# Arduino-Teensy-v421_PLUS_ESP-12E.net
KiCad netlist of a schematic drawn in EAGLE
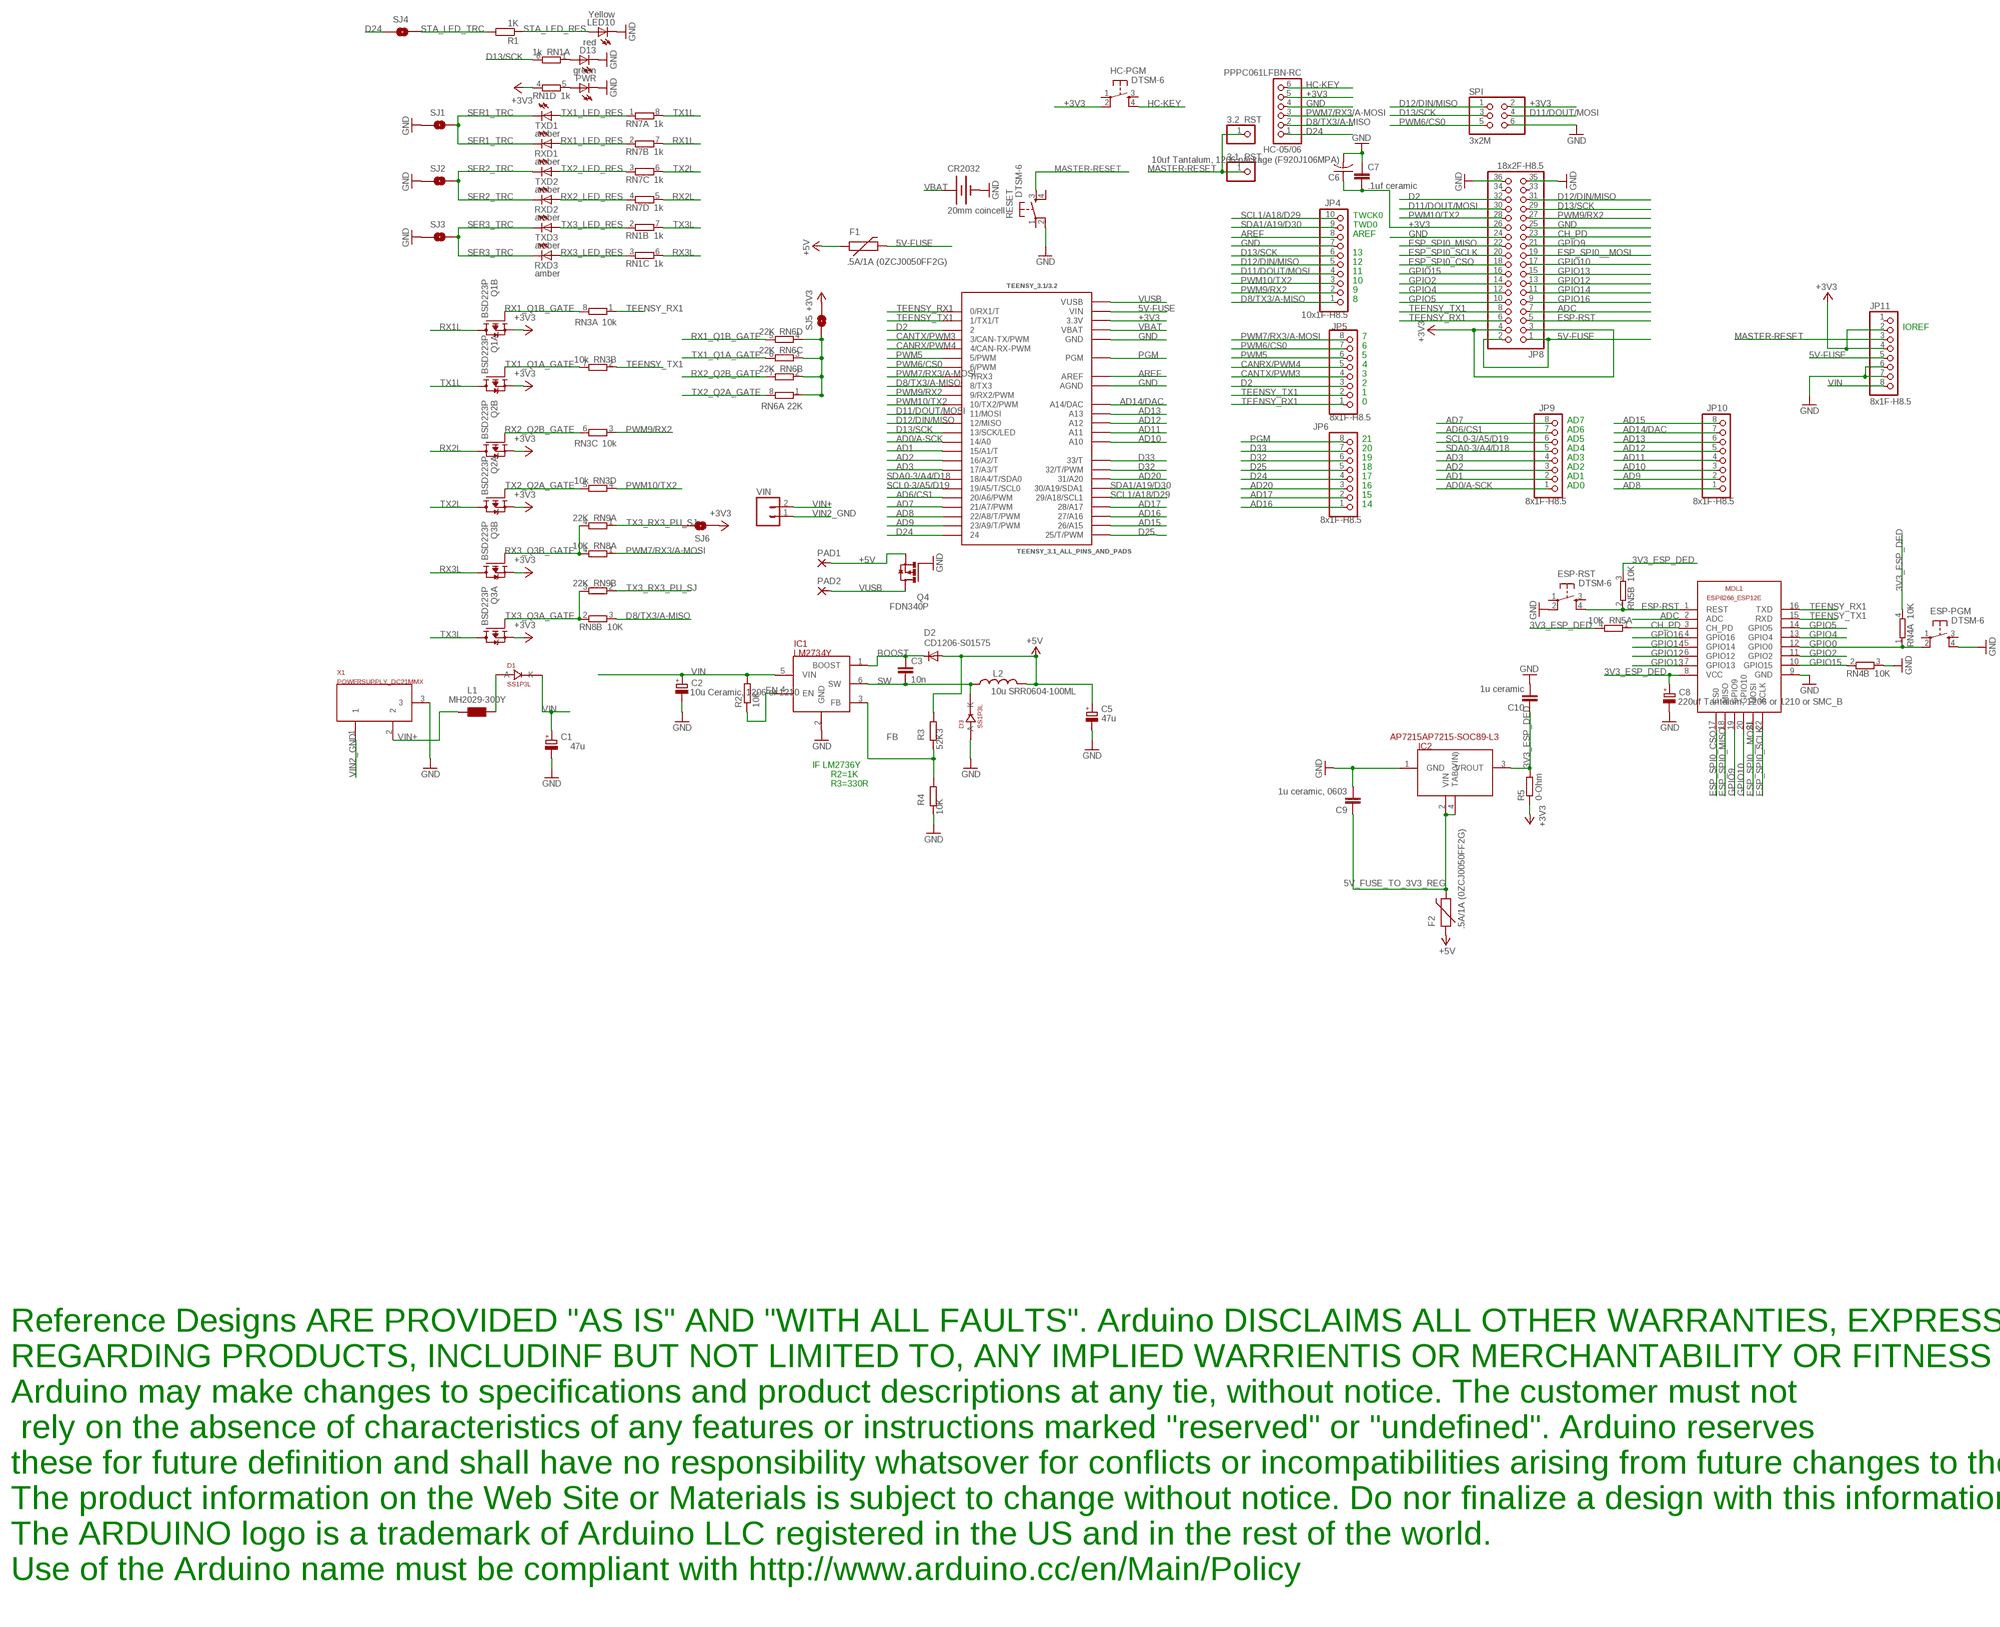
[diagram p0: schematic, sheet 1, part 1 of 2]
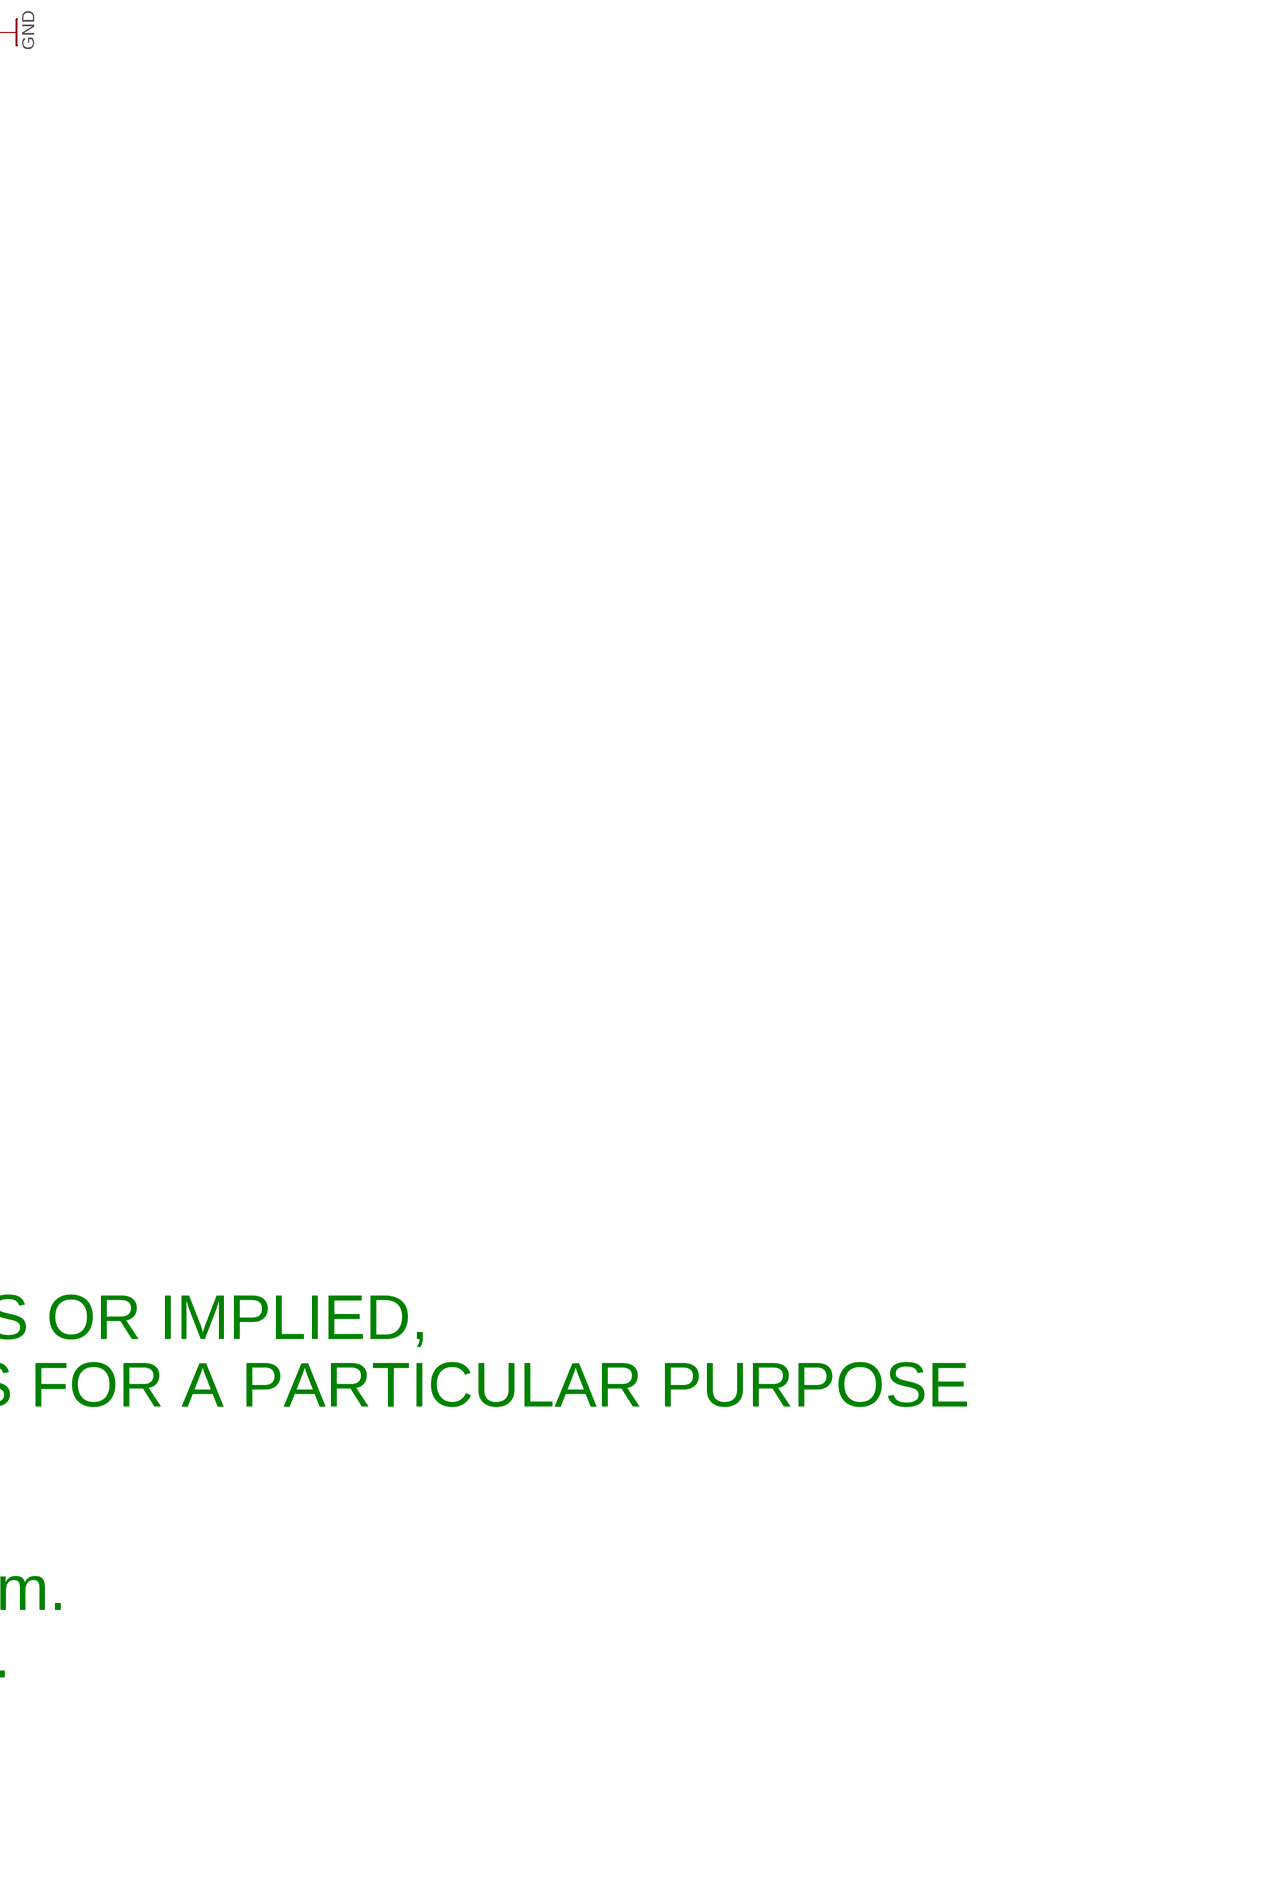
[diagram p1: schematic, sheet 1, part 2 of 2]

(export (version "E")
  (design (tool "Eeschema 10.0.6"))
  (components
    (comp (ref "3.1_RST")
      (value "PINHD-1X1CB")
      (footprint "eagle-import:1X01-CLEANBIG")
      (libsource (lib "eagle-import") (part "PINHD-1X1CB"))
    )
    (comp (ref "3.2_RST")
      (value "PINHD-1X1CB")
      (footprint "eagle-import:1X01-CLEANBIG")
      (libsource (lib "eagle-import") (part "PINHD-1X1CB"))
    )
    (comp (ref "C1")
      (value "47u")
      (footprint "eagle-import:PANASONIC_D")
      (libsource (lib "eagle-import") (part "CPOL-EUD"))
    )
    (comp (ref "C2")
      (value "10u Ceramic, 1206 or 1210")
      (footprint "eagle-import:SMC_B")
      (libsource (lib "eagle-import") (part "CPOL-EUSMCB"))
    )
    (comp (ref "C3")
      (value "10n")
      (footprint "eagle-import:C0603-ROUND")
      (libsource (lib "eagle-import") (part "C-EUC0603"))
    )
    (comp (ref "C5")
      (value "47u")
      (footprint "eagle-import:PANASONIC_D")
      (libsource (lib "eagle-import") (part "CPOL-EUD"))
    )
    (comp (ref "C6")
      (value "10uf Tantalum, 1206 package (F920J106MPA)")
      (footprint "eagle-import:C0805")
      (libsource (lib "eagle-import") (part "C-USC0805"))
    )
    (comp (ref "C7")
      (value ".1uf ceramic")
      (footprint "eagle-import:C0603-ROUND")
      (libsource (lib "eagle-import") (part "C-EUC0603"))
    )
    (comp (ref "C8")
      (value "220uf Tantalum, 1206 or 1210 or SMC_B")
      (footprint "eagle-import:SMC_B")
      (libsource (lib "eagle-import") (part "CPOL-EUSMCB"))
    )
    (comp (ref "C9")
      (value "1u ceramic, 0603")
      (footprint "eagle-import:C0603-ROUND")
      (libsource (lib "eagle-import") (part "C-EUC0603"))
    )
    (comp (ref "C10")
      (value "1u ceramic")
      (footprint "eagle-import:C0603-ROUND")
      (libsource (lib "eagle-import") (part "C-EUC0603"))
    )
    (comp (ref "CR2032")
      (value "20mm coincell")
      (footprint "eagle-import:BATTCON_20MM_4LEGS")
      (libsource (lib "eagle-import") (part "BATTERY20MM_4LEGS"))
    )
    (comp (ref "D1")
      (value "SS1P3L")
      (footprint "eagle-import:DO220AAL")
      (libsource (lib "eagle-import") (part "SS1P3L"))
    )
    (comp (ref "D2")
      (value "CD1206-S01575")
      (footprint "eagle-import:MINIMELF")
      (libsource (lib "eagle-import") (part "DIODE-MINIMELF"))
    )
    (comp (ref "D3")
      (value "SS1P3L")
      (footprint "eagle-import:DO220AAL")
      (libsource (lib "eagle-import") (part "SS1P3L"))
    )
    (comp (ref "D13")
      (value "red")
      (footprint "eagle-import:CHIPLED_0805")
      (libsource (lib "eagle-import") (part "LEDCHIPLED_0805"))
    )
    (comp (ref "ESP-PGM")
      (value "DTSM-6")
      (footprint "eagle-import:DTSM-6")
      (libsource (lib "eagle-import") (part "DTSM-6"))
    )
    (comp (ref "ESP-RST")
      (value "DTSM-6")
      (footprint "eagle-import:DTSM-6")
      (libsource (lib "eagle-import") (part "DTSM-6"))
    )
    (comp (ref "F1")
      (value ".5A/1A (0ZCJ0050FF2G)")
      (footprint "eagle-import:PTC-1206")
      (libsource (lib "eagle-import") (part "PTCSMD"))
    )
    (comp (ref "F2")
      (value ".5A/1A (0ZCJ0050FF2G)")
      (footprint "eagle-import:PTC-1206")
      (libsource (lib "eagle-import") (part "PTCSMD"))
    )
    (comp (ref "HC-05/06")
      (value "PPPC061LFBN-RC")
      (footprint "eagle-import:1X06")
      (libsource (lib "eagle-import") (part "PINHD-1X6"))
    )
    (comp (ref "HC-PGM")
      (value "DTSM-6")
      (footprint "eagle-import:DTSM-6")
      (libsource (lib "eagle-import") (part "DTSM-6"))
    )
    (comp (ref "IC1")
      (value "LM2734Y")
      (footprint "eagle-import:SOT23-6")
      (libsource (lib "eagle-import") (part "LM2736Y"))
    )
    (comp (ref "IC2")
      (value "AP7215AP7215-SOC89-L3")
      (footprint "eagle-import:SOC89-L3")
      (libsource (lib "eagle-import") (part "AP7215AP7215-SOC89-L3"))
    )
    (comp (ref "JP4")
      (value "10x1F-H8.5")
      (footprint "eagle-import:1X10")
      (libsource (lib "eagle-import") (part "PINHD-1X10"))
    )
    (comp (ref "JP5")
      (value "8x1F-H8.5")
      (footprint "eagle-import:1X08")
      (libsource (lib "eagle-import") (part "PINHD-1X8"))
    )
    (comp (ref "JP6")
      (value "8x1F-H8.5")
      (footprint "eagle-import:1X08")
      (libsource (lib "eagle-import") (part "PINHD-1X8"))
    )
    (comp (ref "JP8")
      (value "18x2F-H8.5")
      (footprint "eagle-import:2X18")
      (libsource (lib "eagle-import") (part "PINHD-2X18"))
    )
    (comp (ref "JP9")
      (value "8x1F-H8.5")
      (footprint "eagle-import:1X08")
      (libsource (lib "eagle-import") (part "PINHD-1X8"))
    )
    (comp (ref "JP10")
      (value "8x1F-H8.5")
      (footprint "eagle-import:1X08")
      (libsource (lib "eagle-import") (part "PINHD-1X8"))
    )
    (comp (ref "JP11")
      (value "8x1F-H8.5")
      (footprint "eagle-import:1X08")
      (libsource (lib "eagle-import") (part "PINHD-1X8"))
    )
    (comp (ref "L1")
      (value "MH2029-300Y")
      (footprint "eagle-import:0805")
      (libsource (lib "eagle-import") (part "WE-CBF_0805"))
    )
    (comp (ref "L2")
      (value "10u SRR0604-100ML")
      (footprint "eagle-import:SRR0604")
      (libsource (lib "eagle-import") (part "L-USSRR0604"))
    )
    (comp (ref "LED10")
      (value "Yellow")
      (footprint "eagle-import:CHIPLED_0805")
      (libsource (lib "eagle-import") (part "LEDCHIPLED_0805"))
    )
    (comp (ref "MDL1")
      (value "ESP8266-12E)")
      (footprint "eagle-import:ESP8266-ESP12E")
      (libsource (lib "eagle-import") (part "ESP8266-12EESP8266-ESP12E"))
    )
    (comp (ref "PAD1")
      (value "SMD2")
      (footprint "eagle-import:SMD1,27-2,54")
      (libsource (lib "eagle-import") (part "SMD2"))
    )
    (comp (ref "PAD2")
      (value "SMD2")
      (footprint "eagle-import:SMD1,27-2,54")
      (libsource (lib "eagle-import") (part "SMD2"))
    )
    (comp (ref "PWR")
      (value "green")
      (footprint "eagle-import:CHIPLED_0805")
      (libsource (lib "eagle-import") (part "LEDCHIPLED_0805"))
    )
    (comp (ref "Q1")
      (value "BSD223P")
      (footprint "eagle-import:SOT363_INFINEON")
      (libsource (lib "eagle-import") (part "BSD223P"))
    )
    (comp (ref "Q2")
      (value "BSD223P")
      (footprint "eagle-import:SOT363_INFINEON")
      (libsource (lib "eagle-import") (part "BSD223P"))
    )
    (comp (ref "Q3")
      (value "BSD223P")
      (footprint "eagle-import:SOT363_INFINEON")
      (libsource (lib "eagle-import") (part "BSD223P"))
    )
    (comp (ref "Q4")
      (value "FDN340P")
      (footprint "eagle-import:SUPER-SOT3")
      (libsource (lib "eagle-import") (part "FDN360P"))
    )
    (comp (ref "R1")
      (value "1K")
      (footprint "eagle-import:R0603")
      (libsource (lib "eagle-import") (part "rcl_R-EU_R0603"))
    )
    (comp (ref "R2")
      (value "10K")
      (footprint "eagle-import:R0603")
      (libsource (lib "eagle-import") (part "rcl_R-EU_R0603"))
    )
    (comp (ref "R3")
      (value "52K3")
      (footprint "eagle-import:R0603-ROUND")
      (libsource (lib "eagle-import") (part "R-EU_0603-RND"))
    )
    (comp (ref "R4")
      (value "10K")
      (footprint "eagle-import:R0603-ROUND")
      (libsource (lib "eagle-import") (part "R-EU_0603-RND"))
    )
    (comp (ref "R5")
      (value "0-Ohm")
      (footprint "eagle-import:R0603")
      (libsource (lib "eagle-import") (part "rcl_R-EU_R0603"))
    )
    (comp (ref "RESET")
      (value "DTSM-6")
      (footprint "eagle-import:DTSM-6")
      (libsource (lib "eagle-import") (part "DTSM-6"))
    )
    (comp (ref "RN1")
      (value "1k")
      (footprint "eagle-import:CAT16")
      (libsource (lib "eagle-import") (part "4R-NCAT16"))
    )
    (comp (ref "RN3")
      (value "10k")
      (footprint "eagle-import:CAT16")
      (libsource (lib "eagle-import") (part "4R-NCAT16"))
    )
    (comp (ref "RN4")
      (value "10K")
      (footprint "eagle-import:EXB34V")
      (libsource (lib "eagle-import") (part "2R-NEXB34V"))
    )
    (comp (ref "RN5")
      (value "10K")
      (footprint "eagle-import:EXB34V")
      (libsource (lib "eagle-import") (part "2R-NEXB34V"))
    )
    (comp (ref "RN6")
      (value "22K")
      (footprint "eagle-import:CAT16")
      (libsource (lib "eagle-import") (part "4R-NCAT16"))
    )
    (comp (ref "RN7")
      (value "1k")
      (footprint "eagle-import:CAT16")
      (libsource (lib "eagle-import") (part "4R-NCAT16"))
    )
    (comp (ref "RN8")
      (value "10K")
      (footprint "eagle-import:EXB34V")
      (libsource (lib "eagle-import") (part "2R-NEXB34V"))
    )
    (comp (ref "RN9")
      (value "22K")
      (footprint "eagle-import:EXB34V")
      (libsource (lib "eagle-import") (part "2R-NEXB34V"))
    )
    (comp (ref "RXD1")
      (value "amber")
      (footprint "eagle-import:CHIPLED_0805")
      (libsource (lib "eagle-import") (part "LEDCHIPLED_0805"))
    )
    (comp (ref "RXD2")
      (value "amber")
      (footprint "eagle-import:CHIPLED_0805")
      (libsource (lib "eagle-import") (part "LEDCHIPLED_0805"))
    )
    (comp (ref "RXD3")
      (value "amber")
      (footprint "eagle-import:CHIPLED_0805")
      (libsource (lib "eagle-import") (part "LEDCHIPLED_0805"))
    )
    (comp (ref "SJ1")
      (value "SOLDERJUMPERTRACE")
      (footprint "eagle-import:SJ_2S-TRACE")
      (libsource (lib "eagle-import") (part "SOLDERJUMPERTRACE"))
    )
    (comp (ref "SJ2")
      (value "SOLDERJUMPERTRACE")
      (footprint "eagle-import:SJ_2S-TRACE")
      (libsource (lib "eagle-import") (part "SOLDERJUMPERTRACE"))
    )
    (comp (ref "SJ3")
      (value "SOLDERJUMPERTRACE")
      (footprint "eagle-import:SJ_2S-TRACE")
      (libsource (lib "eagle-import") (part "SOLDERJUMPERTRACE"))
    )
    (comp (ref "SJ4")
      (value "SOLDERJUMPERTRACE")
      (footprint "eagle-import:SJ_2S-TRACE")
      (libsource (lib "eagle-import") (part "SOLDERJUMPERTRACE"))
    )
    (comp (ref "SJ5")
      (value "SOLDERJUMPERTRACE")
      (footprint "eagle-import:SJ_2S-TRACE")
      (libsource (lib "eagle-import") (part "SOLDERJUMPERTRACE"))
    )
    (comp (ref "SJ6")
      (value "SOLDERJUMPERTRACE")
      (footprint "eagle-import:SJ_2S-TRACE")
      (libsource (lib "eagle-import") (part "SOLDERJUMPERTRACE"))
    )
    (comp (ref "SPI")
      (value "3x2M")
      (footprint "eagle-import:2X03")
      (libsource (lib "eagle-import") (part "PINHD-2X3"))
    )
    (comp (ref "TEENSY_3.1/3.2")
      (value "TEENSY_3.1_ALL_PINS_AND_PADS")
      (footprint "eagle-import:TEENSY3_ALL_PINS_&_PADS")
      (libsource (lib "eagle-import") (part "TEENSY_3.1_ALL_PINS_AND_PADS"))
    )
    (comp (ref "TXD1")
      (value "amber")
      (footprint "eagle-import:CHIPLED_0805")
      (libsource (lib "eagle-import") (part "LEDCHIPLED_0805"))
    )
    (comp (ref "TXD2")
      (value "amber")
      (footprint "eagle-import:CHIPLED_0805")
      (libsource (lib "eagle-import") (part "LEDCHIPLED_0805"))
    )
    (comp (ref "TXD3")
      (value "amber")
      (footprint "eagle-import:CHIPLED_0805")
      (libsource (lib "eagle-import") (part "LEDCHIPLED_0805"))
    )
    (comp (ref "VIN")
      (value "M02LOCK_LONGPADS")
      (footprint "eagle-import:1X02_LOCK_LONGPADS")
      (libsource (lib "eagle-import") (part "M02LOCK_LONGPADS"))
    )
    (comp (ref "X1")
      (value "POWERSUPPLY_DC21MMX")
      (footprint "eagle-import:POWERSUPPLY_DC-21MM")
      (libsource (lib "eagle-import") (part "POWERSUPPLY_DC21MMX"))
    )
  )
  (nets
    (net (code "1") (name "+3V3") (class "Default")
      (node (ref "C6") (pin "1") (pinfunction "1_1") (pintype "passive"))
      (node (ref "C7") (pin "2") (pinfunction "2_2") (pintype "passive"))
      (node (ref "HC-05/06") (pin "5") (pinfunction "5_5") (pintype "passive"))
      (node (ref "HC-PGM") (pin "2") (pinfunction "2_2") (pintype "passive"))
      (node (ref "JP11") (pin "2") (pinfunction "2_2") (pintype "passive"))
      (node (ref "JP11") (pin "4") (pinfunction "4_4") (pintype "passive"))
      (node (ref "JP8") (pin "26") (pinfunction "26_26") (pintype "passive"))
      (node (ref "JP8") (pin "3") (pinfunction "3_3") (pintype "passive"))
      (node (ref "JP8") (pin "4") (pinfunction "4_4") (pintype "passive"))
      (node (ref "Q1") (pin "1") (pinfunction "S_1") (pintype "passive"))
      (node (ref "Q1") (pin "4") (pinfunction "S_4") (pintype "passive"))
      (node (ref "Q2") (pin "1") (pinfunction "S_1") (pintype "passive"))
      (node (ref "Q2") (pin "4") (pinfunction "S_4") (pintype "passive"))
      (node (ref "Q3") (pin "1") (pinfunction "S_1") (pintype "passive"))
      (node (ref "Q3") (pin "4") (pinfunction "S_4") (pintype "passive"))
      (node (ref "R5") (pin "1") (pinfunction "1_1") (pintype "passive"))
      (node (ref "RN1") (pin "4") (pinfunction "1_4") (pintype "passive"))
      (node (ref "SJ5") (pin "2") (pinfunction "2_2") (pintype "passive"))
      (node (ref "SJ6") (pin "1") (pinfunction "1_1") (pintype "passive"))
      (node (ref "SPI") (pin "2") (pinfunction "2_2") (pintype "passive"))
      (node (ref "TEENSY_3.1/3.2") (pin "3.3V") (pinfunction "3.3V_3.3V") (pintype "power_in"))
      (node (ref "TEENSY_3.1/3.2") (pin "3.3V1") (pinfunction "3.3V_3.3V1") (pintype "power_in"))
      (node (ref "TEENSY_3.1/3.2") (pin "3.3V2") (pinfunction "3.3V_3.3V2") (pintype "power_in"))
    )
    (net (code "2") (name "+5V") (class "Default")
      (node (ref "C5") (pin "+") (pinfunction "+_+") (pintype "passive"))
      (node (ref "D2") (pin "A") (pinfunction "A_A") (pintype "passive"))
      (node (ref "F1") (pin "1") (pinfunction "1_1") (pintype "bidirectional"))
      (node (ref "F2") (pin "1") (pinfunction "1_1") (pintype "bidirectional"))
      (node (ref "L2") (pin "P$2") (pinfunction "2_P$2") (pintype "passive"))
      (node (ref "PAD1") (pin "1") (pinfunction "P_1") (pintype "passive"))
      (node (ref "Q4") (pin "2") (pinfunction "S_2") (pintype "passive"))
      (node (ref "R3") (pin "1") (pinfunction "1_1") (pintype "passive"))
    )
    (net (code "3") (name "/3V3_ESP_DED") (class "Default")
      (node (ref "C10") (pin "1") (pinfunction "1_1") (pintype "passive"))
      (node (ref "C8") (pin "+") (pinfunction "+_+") (pintype "passive"))
      (node (ref "IC2") (pin "3") (pinfunction "VROUT_3") (pintype "output"))
      (node (ref "MDL1") (pin "8") (pinfunction "VCC_8") (pintype "bidirectional"))
      (node (ref "R5") (pin "2") (pinfunction "2_2") (pintype "passive"))
      (node (ref "RN4") (pin "4") (pinfunction "2_4") (pintype "passive"))
      (node (ref "RN5") (pin "3") (pinfunction "2_3") (pintype "passive"))
      (node (ref "RN5") (pin "4") (pinfunction "2_4") (pintype "passive"))
    )
    (net (code "4") (name "/5V-FUSE") (class "Default")
      (node (ref "F1") (pin "2") (pinfunction "2_2") (pintype "bidirectional"))
      (node (ref "JP11") (pin "5") (pinfunction "5_5") (pintype "passive"))
      (node (ref "JP8") (pin "1") (pinfunction "1_1") (pintype "passive"))
      (node (ref "JP8") (pin "2") (pinfunction "2_2") (pintype "passive"))
      (node (ref "TEENSY_3.1/3.2") (pin "VIN") (pinfunction "VIN_VIN") (pintype "power_in"))
    )
    (net (code "5") (name "/5V_FUSE_TO_3V3_REG") (class "Default")
      (node (ref "C9") (pin "1") (pinfunction "1_1") (pintype "passive"))
      (node (ref "F2") (pin "2") (pinfunction "2_2") (pintype "bidirectional"))
      (node (ref "IC2") (pin "2") (pinfunction "VIN_2") (pintype "input"))
      (node (ref "IC2") (pin "4") (pinfunction "TAB(VIN)_4") (pintype "input"))
    )
    (net (code "6") (name "/AD0{slash}A-SCK") (class "Default")
      (node (ref "JP9") (pin "1") (pinfunction "1_1") (pintype "passive"))
      (node (ref "TEENSY_3.1/3.2") (pin "14/A0") (pinfunction "14/A0_14/A0") (pintype "bidirectional"))
    )
    (net (code "7") (name "/AD1") (class "Default")
      (node (ref "JP9") (pin "2") (pinfunction "2_2") (pintype "passive"))
      (node (ref "TEENSY_3.1/3.2") (pin "15/A1") (pinfunction "15/A1/T_15/A1") (pintype "bidirectional"))
    )
    (net (code "8") (name "/AD2") (class "Default")
      (node (ref "JP9") (pin "3") (pinfunction "3_3") (pintype "passive"))
      (node (ref "TEENSY_3.1/3.2") (pin "16/A2") (pinfunction "16/A2/T_16/A2") (pintype "bidirectional"))
    )
    (net (code "9") (name "/AD3") (class "Default")
      (node (ref "JP9") (pin "4") (pinfunction "4_4") (pintype "passive"))
      (node (ref "TEENSY_3.1/3.2") (pin "17/A3") (pinfunction "17/A3/T_17/A3") (pintype "bidirectional"))
    )
    (net (code "10") (name "/AD6{slash}CS1") (class "Default")
      (node (ref "JP9") (pin "7") (pinfunction "7_7") (pintype "passive"))
      (node (ref "TEENSY_3.1/3.2") (pin "20/A6") (pinfunction "20/A6/PWM_20/A6") (pintype "bidirectional"))
    )
    (net (code "11") (name "/AD7") (class "Default")
      (node (ref "JP9") (pin "8") (pinfunction "8_8") (pintype "passive"))
      (node (ref "TEENSY_3.1/3.2") (pin "21/A7") (pinfunction "21/A7/PWM_21/A7") (pintype "bidirectional"))
    )
    (net (code "12") (name "/AD8") (class "Default")
      (node (ref "JP10") (pin "1") (pinfunction "1_1") (pintype "passive"))
      (node (ref "TEENSY_3.1/3.2") (pin "22/A8") (pinfunction "22/A8/T/PWM_22/A8") (pintype "bidirectional"))
    )
    (net (code "13") (name "/AD9") (class "Default")
      (node (ref "JP10") (pin "2") (pinfunction "2_2") (pintype "passive"))
      (node (ref "TEENSY_3.1/3.2") (pin "23/A9") (pinfunction "23/A9/T/PWM_23/A9") (pintype "bidirectional"))
    )
    (net (code "14") (name "/AD10") (class "Default")
      (node (ref "JP10") (pin "3") (pinfunction "3_3") (pintype "passive"))
      (node (ref "TEENSY_3.1/3.2") (pin "A10") (pinfunction "A10_A10") (pintype "bidirectional"))
    )
    (net (code "15") (name "/AD11") (class "Default")
      (node (ref "JP10") (pin "4") (pinfunction "4_4") (pintype "passive"))
      (node (ref "TEENSY_3.1/3.2") (pin "A11") (pinfunction "A11_A11") (pintype "bidirectional"))
    )
    (net (code "16") (name "/AD12") (class "Default")
      (node (ref "JP10") (pin "5") (pinfunction "5_5") (pintype "passive"))
      (node (ref "TEENSY_3.1/3.2") (pin "A12") (pinfunction "A12_A12") (pintype "bidirectional"))
    )
    (net (code "17") (name "/AD13") (class "Default")
      (node (ref "JP10") (pin "6") (pinfunction "6_6") (pintype "passive"))
      (node (ref "TEENSY_3.1/3.2") (pin "A13") (pinfunction "A13_A13") (pintype "bidirectional"))
    )
    (net (code "18") (name "/AD14{slash}DAC") (class "Default")
      (node (ref "JP10") (pin "7") (pinfunction "7_7") (pintype "passive"))
      (node (ref "TEENSY_3.1/3.2") (pin "RESET/DAC") (pinfunction "A14/DAC_RESET/DAC") (pintype "bidirectional"))
    )
    (net (code "19") (name "/AD15") (class "Default")
      (node (ref "JP10") (pin "8") (pinfunction "8_8") (pintype "passive"))
      (node (ref "TEENSY_3.1/3.2") (pin "26") (pinfunction "26/A15_26") (pintype "bidirectional"))
    )
    (net (code "20") (name "/AD16") (class "Default")
      (node (ref "JP6") (pin "1") (pinfunction "1_1") (pintype "passive"))
      (node (ref "TEENSY_3.1/3.2") (pin "27") (pinfunction "27/A16_27") (pintype "bidirectional"))
    )
    (net (code "21") (name "/AD17") (class "Default")
      (node (ref "JP6") (pin "2") (pinfunction "2_2") (pintype "passive"))
      (node (ref "TEENSY_3.1/3.2") (pin "28") (pinfunction "28/A17_28") (pintype "bidirectional"))
    )
    (net (code "22") (name "/AD20") (class "Default")
      (node (ref "JP6") (pin "3") (pinfunction "3_3") (pintype "passive"))
      (node (ref "TEENSY_3.1/3.2") (pin "31") (pinfunction "31/A20_31") (pintype "bidirectional"))
    )
    (net (code "23") (name "/ADC") (class "Default")
      (node (ref "JP8") (pin "7") (pinfunction "7_7") (pintype "passive"))
      (node (ref "MDL1") (pin "2") (pinfunction "ADC_2") (pintype "bidirectional"))
    )
    (net (code "24") (name "/AREF") (class "Default")
      (node (ref "JP4") (pin "8") (pinfunction "8_8") (pintype "passive"))
      (node (ref "TEENSY_3.1/3.2") (pin "AREF") (pinfunction "AREF_AREF") (pintype "power_in"))
    )
    (net (code "25") (name "/BOOST") (class "Default")
      (node (ref "C3") (pin "1") (pinfunction "1_1") (pintype "passive"))
      (node (ref "D2") (pin "C") (pinfunction "C_C") (pintype "passive"))
      (node (ref "IC1") (pin "1") (pinfunction "BOOST_1") (pintype "input"))
    )
    (net (code "26") (name "/CANRX{slash}PWM4") (class "Default")
      (node (ref "JP5") (pin "5") (pinfunction "5_5") (pintype "passive"))
      (node (ref "TEENSY_3.1/3.2") (pin "4") (pinfunction "4/CAN-RX-PWM_4") (pintype "bidirectional"))
    )
    (net (code "27") (name "/CANTX{slash}PWM3") (class "Default")
      (node (ref "JP5") (pin "4") (pinfunction "4_4") (pintype "passive"))
      (node (ref "TEENSY_3.1/3.2") (pin "3") (pinfunction "3/CAN-TX/PWM_3") (pintype "bidirectional"))
    )
    (net (code "28") (name "/CH_PD") (class "Default")
      (node (ref "JP8") (pin "23") (pinfunction "23_23") (pintype "passive"))
      (node (ref "MDL1") (pin "3") (pinfunction "CH_PD_3") (pintype "bidirectional"))
      (node (ref "RN5") (pin "1") (pinfunction "1_1") (pintype "passive"))
    )
    (net (code "29") (name "/D2") (class "Default")
      (node (ref "JP5") (pin "3") (pinfunction "3_3") (pintype "passive"))
      (node (ref "JP8") (pin "32") (pinfunction "32_32") (pintype "passive"))
      (node (ref "TEENSY_3.1/3.2") (pin "2") (pinfunction "2_2") (pintype "bidirectional"))
    )
    (net (code "30") (name "/D8{slash}TX3{slash}A-MISO") (class "Default")
      (node (ref "HC-05/06") (pin "2") (pinfunction "2_2") (pintype "passive"))
      (node (ref "JP4") (pin "1") (pinfunction "1_1") (pintype "passive"))
      (node (ref "RN8") (pin "3") (pinfunction "2_3") (pintype "passive"))
      (node (ref "TEENSY_3.1/3.2") (pin "8") (pinfunction "8/TX3_8") (pintype "bidirectional"))
    )
    (net (code "31") (name "/D11{slash}DOUT{slash}MOSI") (class "Default")
      (node (ref "JP4") (pin "4") (pinfunction "4_4") (pintype "passive"))
      (node (ref "JP8") (pin "30") (pinfunction "30_30") (pintype "passive"))
      (node (ref "SPI") (pin "4") (pinfunction "4_4") (pintype "passive"))
      (node (ref "TEENSY_3.1/3.2") (pin "11") (pinfunction "11/MOSI_11") (pintype "bidirectional"))
    )
    (net (code "32") (name "/D12{slash}DIN{slash}MISO") (class "Default")
      (node (ref "JP4") (pin "5") (pinfunction "5_5") (pintype "passive"))
      (node (ref "JP8") (pin "31") (pinfunction "31_31") (pintype "passive"))
      (node (ref "SPI") (pin "1") (pinfunction "1_1") (pintype "passive"))
      (node (ref "TEENSY_3.1/3.2") (pin "12") (pinfunction "12/MISO_12") (pintype "bidirectional"))
    )
    (net (code "33") (name "/D13{slash}SCK") (class "Default")
      (node (ref "JP4") (pin "6") (pinfunction "6_6") (pintype "passive"))
      (node (ref "JP8") (pin "29") (pinfunction "29_29") (pintype "passive"))
      (node (ref "RN1") (pin "8") (pinfunction "2_8") (pintype "passive"))
      (node (ref "SPI") (pin "3") (pinfunction "3_3") (pintype "passive"))
      (node (ref "TEENSY_3.1/3.2") (pin "13") (pinfunction "13/SCK/LED_13") (pintype "bidirectional"))
    )
    (net (code "34") (name "/D24") (class "Default")
      (node (ref "HC-05/06") (pin "1") (pinfunction "1_1") (pintype "passive"))
      (node (ref "JP6") (pin "4") (pinfunction "4_4") (pintype "passive"))
      (node (ref "SJ4") (pin "1") (pinfunction "1_1") (pintype "passive"))
      (node (ref "TEENSY_3.1/3.2") (pin "24") (pinfunction "24_24") (pintype "bidirectional"))
    )
    (net (code "35") (name "/D25") (class "Default")
      (node (ref "JP6") (pin "5") (pinfunction "5_5") (pintype "passive"))
      (node (ref "TEENSY_3.1/3.2") (pin "25") (pinfunction "25/T/PWM_25") (pintype "bidirectional"))
    )
    (net (code "36") (name "/D32") (class "Default")
      (node (ref "JP6") (pin "6") (pinfunction "6_6") (pintype "passive"))
      (node (ref "TEENSY_3.1/3.2") (pin "32") (pinfunction "32/T/PWM_32") (pintype "bidirectional"))
    )
    (net (code "37") (name "/D33") (class "Default")
      (node (ref "JP6") (pin "7") (pinfunction "7_7") (pintype "passive"))
      (node (ref "TEENSY_3.1/3.2") (pin "33") (pinfunction "33/T_33") (pintype "bidirectional"))
    )
    (net (code "38") (name "/EN") (class "Default")
      (node (ref "IC1") (pin "4") (pinfunction "EN_4") (pintype "input"))
      (node (ref "R2") (pin "1") (pinfunction "1_1") (pintype "passive"))
    )
    (net (code "39") (name "/ESP-RST") (class "Default")
      (node (ref "ESP-RST") (pin "4") (pinfunction "4_4") (pintype "passive"))
      (node (ref "JP8") (pin "5") (pinfunction "5_5") (pintype "passive"))
      (node (ref "MDL1") (pin "1") (pinfunction "REST_1") (pintype "bidirectional"))
      (node (ref "RN5") (pin "2") (pinfunction "1_2") (pintype "passive"))
    )
    (net (code "40") (name "/ESP_SPI0_CSO") (class "Default")
      (node (ref "JP8") (pin "18") (pinfunction "18_18") (pintype "passive"))
      (node (ref "MDL1") (pin "17") (pinfunction "CS0_17") (pintype "bidirectional"))
    )
    (net (code "41") (name "/ESP_SPI0_MISO") (class "Default")
      (node (ref "JP8") (pin "22") (pinfunction "22_22") (pintype "passive"))
      (node (ref "MDL1") (pin "18") (pinfunction "MISO_18") (pintype "bidirectional"))
    )
    (net (code "42") (name "/ESP_SPI0_SCLK") (class "Default")
      (node (ref "JP8") (pin "20") (pinfunction "20_20") (pintype "passive"))
      (node (ref "MDL1") (pin "22") (pinfunction "SCLK_22") (pintype "bidirectional"))
    )
    (net (code "43") (name "/ESP_SPI0__MOSI") (class "Default")
      (node (ref "JP8") (pin "19") (pinfunction "19_19") (pintype "passive"))
      (node (ref "MDL1") (pin "21") (pinfunction "MOSI_21") (pintype "bidirectional"))
    )
    (net (code "44") (name "/FB") (class "Default")
      (node (ref "IC1") (pin "3") (pinfunction "FB_3") (pintype "input"))
      (node (ref "R3") (pin "2") (pinfunction "2_2") (pintype "passive"))
      (node (ref "R4") (pin "1") (pinfunction "1_1") (pintype "passive"))
    )
    (net (code "45") (name "/GPIO0") (class "Default")
      (node (ref "ESP-PGM") (pin "2") (pinfunction "2_2") (pintype "passive"))
      (node (ref "MDL1") (pin "12") (pinfunction "GPIO0_12") (pintype "bidirectional"))
      (node (ref "RN4") (pin "1") (pinfunction "1_1") (pintype "passive"))
    )
    (net (code "46") (name "/GPIO2") (class "Default")
      (node (ref "JP8") (pin "14") (pinfunction "14_14") (pintype "passive"))
      (node (ref "MDL1") (pin "11") (pinfunction "GPIO2_11") (pintype "bidirectional"))
    )
    (net (code "47") (name "/GPIO4") (class "Default")
      (node (ref "JP8") (pin "12") (pinfunction "12_12") (pintype "passive"))
      (node (ref "MDL1") (pin "13") (pinfunction "GPIO4_13") (pintype "bidirectional"))
    )
    (net (code "48") (name "/GPIO5") (class "Default")
      (node (ref "JP8") (pin "10") (pinfunction "10_10") (pintype "passive"))
      (node (ref "MDL1") (pin "14") (pinfunction "GPIO5_14") (pintype "bidirectional"))
    )
    (net (code "49") (name "/GPIO9") (class "Default")
      (node (ref "JP8") (pin "21") (pinfunction "21_21") (pintype "passive"))
      (node (ref "MDL1") (pin "19") (pinfunction "GPIO9_19") (pintype "bidirectional"))
    )
    (net (code "50") (name "/GPIO10") (class "Default")
      (node (ref "JP8") (pin "17") (pinfunction "17_17") (pintype "passive"))
      (node (ref "MDL1") (pin "20") (pinfunction "GPIO10_20") (pintype "bidirectional"))
    )
    (net (code "51") (name "/GPIO12") (class "Default")
      (node (ref "JP8") (pin "13") (pinfunction "13_13") (pintype "passive"))
      (node (ref "MDL1") (pin "6") (pinfunction "GPIO12_6") (pintype "bidirectional"))
    )
    (net (code "52") (name "/GPIO13") (class "Default")
      (node (ref "JP8") (pin "15") (pinfunction "15_15") (pintype "passive"))
      (node (ref "MDL1") (pin "7") (pinfunction "GPIO13_7") (pintype "bidirectional"))
    )
    (net (code "53") (name "/GPIO14") (class "Default")
      (node (ref "JP8") (pin "11") (pinfunction "11_11") (pintype "passive"))
      (node (ref "MDL1") (pin "5") (pinfunction "GPIO14_5") (pintype "bidirectional"))
    )
    (net (code "54") (name "/GPIO15") (class "Default")
      (node (ref "JP8") (pin "16") (pinfunction "16_16") (pintype "passive"))
      (node (ref "MDL1") (pin "10") (pinfunction "GPIO15_10") (pintype "bidirectional"))
      (node (ref "RN4") (pin "2") (pinfunction "1_2") (pintype "passive"))
    )
    (net (code "55") (name "/GPIO16") (class "Default")
      (node (ref "JP8") (pin "9") (pinfunction "9_9") (pintype "passive"))
      (node (ref "MDL1") (pin "4") (pinfunction "GPIO16_4") (pintype "bidirectional"))
    )
    (net (code "56") (name "/HC-KEY") (class "Default")
      (node (ref "HC-05/06") (pin "6") (pinfunction "6_6") (pintype "passive"))
      (node (ref "HC-PGM") (pin "4") (pinfunction "4_4") (pintype "passive"))
    )
    (net (code "57") (name "/MASTER-RESET") (class "Default")
      (node (ref "3.1_RST") (pin "1") (pinfunction "1_1") (pintype "passive"))
      (node (ref "3.2_RST") (pin "1") (pinfunction "1_1") (pintype "passive"))
      (node (ref "JP11") (pin "3") (pinfunction "3_3") (pintype "passive"))
      (node (ref "RESET") (pin "3") (pinfunction "3_3") (pintype "passive"))
    )
    (net (code "58") (name "/PGM") (class "Default")
      (node (ref "JP6") (pin "8") (pinfunction "8_8") (pintype "passive"))
      (node (ref "TEENSY_3.1/3.2") (pin "PGM") (pinfunction "PGM_PGM") (pintype "bidirectional"))
    )
    (net (code "59") (name "/PWM5") (class "Default")
      (node (ref "JP5") (pin "6") (pinfunction "6_6") (pintype "passive"))
      (node (ref "TEENSY_3.1/3.2") (pin "5") (pinfunction "5/PWM_5") (pintype "bidirectional"))
    )
    (net (code "60") (name "/PWM6{slash}CS0") (class "Default")
      (node (ref "JP5") (pin "7") (pinfunction "7_7") (pintype "passive"))
      (node (ref "SPI") (pin "5") (pinfunction "5_5") (pintype "passive"))
      (node (ref "TEENSY_3.1/3.2") (pin "6") (pinfunction "6/PWM_6") (pintype "bidirectional"))
    )
    (net (code "61") (name "/PWM7{slash}RX3{slash}A-MOSI") (class "Default")
      (node (ref "HC-05/06") (pin "3") (pinfunction "3_3") (pintype "passive"))
      (node (ref "JP5") (pin "8") (pinfunction "8_8") (pintype "passive"))
      (node (ref "RN8") (pin "1") (pinfunction "1_1") (pintype "passive"))
      (node (ref "TEENSY_3.1/3.2") (pin "7") (pinfunction "7/RX3_7") (pintype "bidirectional"))
    )
    (net (code "62") (name "/PWM9{slash}RX2") (class "Default")
      (node (ref "JP4") (pin "2") (pinfunction "2_2") (pintype "passive"))
      (node (ref "JP8") (pin "27") (pinfunction "27_27") (pintype "passive"))
      (node (ref "RN3") (pin "3") (pinfunction "1_3") (pintype "passive"))
      (node (ref "TEENSY_3.1/3.2") (pin "9") (pinfunction "9/RX2/PWM_9") (pintype "bidirectional"))
    )
    (net (code "63") (name "/PWM10{slash}TX2") (class "Default")
      (node (ref "JP4") (pin "3") (pinfunction "3_3") (pintype "passive"))
      (node (ref "JP8") (pin "28") (pinfunction "28_28") (pintype "passive"))
      (node (ref "RN3") (pin "4") (pinfunction "1_4") (pintype "passive"))
      (node (ref "TEENSY_3.1/3.2") (pin "10") (pinfunction "10/TX2/PWM_10") (pintype "bidirectional"))
    )
    (net (code "64") (name "/RX1L") (class "Default")
      (node (ref "Q1") (pin "3") (pinfunction "D_3") (pintype "passive"))
      (node (ref "RN7") (pin "7") (pinfunction "2_7") (pintype "passive"))
    )
    (net (code "65") (name "/RX1_LED_RES") (class "Default")
      (node (ref "RN7") (pin "2") (pinfunction "1_2") (pintype "passive"))
      (node (ref "RXD1") (pin "A") (pinfunction "A_A") (pintype "passive"))
    )
    (net (code "66") (name "/RX1_Q1B_GATE") (class "Default")
      (node (ref "Q1") (pin "5") (pinfunction "G_5") (pintype "passive"))
      (node (ref "RN3") (pin "8") (pinfunction "2_8") (pintype "passive"))
      (node (ref "RN6") (pin "5") (pinfunction "2_5") (pintype "passive"))
    )
    (net (code "67") (name "/RX2L") (class "Default")
      (node (ref "Q2") (pin "3") (pinfunction "D_3") (pintype "passive"))
      (node (ref "RN7") (pin "5") (pinfunction "2_5") (pintype "passive"))
    )
    (net (code "68") (name "/RX2_LED_RES") (class "Default")
      (node (ref "RN7") (pin "4") (pinfunction "1_4") (pintype "passive"))
      (node (ref "RXD2") (pin "A") (pinfunction "A_A") (pintype "passive"))
    )
    (net (code "69") (name "/RX2_Q2B_GATE") (class "Default")
      (node (ref "Q2") (pin "5") (pinfunction "G_5") (pintype "passive"))
      (node (ref "RN3") (pin "6") (pinfunction "2_6") (pintype "passive"))
      (node (ref "RN6") (pin "7") (pinfunction "2_7") (pintype "passive"))
    )
    (net (code "70") (name "/RX3L") (class "Default")
      (node (ref "Q3") (pin "3") (pinfunction "D_3") (pintype "passive"))
      (node (ref "RN1") (pin "6") (pinfunction "2_6") (pintype "passive"))
    )
    (net (code "71") (name "/RX3_LED_RES") (class "Default")
      (node (ref "RN1") (pin "3") (pinfunction "1_3") (pintype "passive"))
      (node (ref "RXD3") (pin "A") (pinfunction "A_A") (pintype "passive"))
    )
    (net (code "72") (name "/RX3_Q3B_GATE") (class "Default")
      (node (ref "Q3") (pin "5") (pinfunction "G_5") (pintype "passive"))
      (node (ref "RN8") (pin "4") (pinfunction "2_4") (pintype "passive"))
      (node (ref "RN9") (pin "4") (pinfunction "2_4") (pintype "passive"))
    )
    (net (code "73") (name "/SCL0-3{slash}A5{slash}D19") (class "Default")
      (node (ref "JP9") (pin "6") (pinfunction "6_6") (pintype "passive"))
      (node (ref "TEENSY_3.1/3.2") (pin "19/A5") (pinfunction "19/A5/T/SCL0_19/A5") (pintype "bidirectional"))
    )
    (net (code "74") (name "/SCL1{slash}A18{slash}D29") (class "Default")
      (node (ref "JP4") (pin "10") (pinfunction "10_10") (pintype "passive"))
      (node (ref "TEENSY_3.1/3.2") (pin "29") (pinfunction "29/A18/SCL1_29") (pintype "bidirectional"))
    )
    (net (code "75") (name "/SDA0-3{slash}A4{slash}D18") (class "Default")
      (node (ref "JP9") (pin "5") (pinfunction "5_5") (pintype "passive"))
      (node (ref "TEENSY_3.1/3.2") (pin "18/A4") (pinfunction "18/A4/T/SDA0_18/A4") (pintype "bidirectional"))
    )
    (net (code "76") (name "/SDA1{slash}A19{slash}D30") (class "Default")
      (node (ref "JP4") (pin "9") (pinfunction "9_9") (pintype "passive"))
      (node (ref "TEENSY_3.1/3.2") (pin "30") (pinfunction "30/A19/SDA1_30") (pintype "bidirectional"))
    )
    (net (code "77") (name "/SER1_TRC") (class "Default")
      (node (ref "RXD1") (pin "C") (pinfunction "C_C") (pintype "passive"))
      (node (ref "SJ1") (pin "2") (pinfunction "2_2") (pintype "passive"))
      (node (ref "TXD1") (pin "C") (pinfunction "C_C") (pintype "passive"))
    )
    (net (code "78") (name "/SER2_TRC") (class "Default")
      (node (ref "RXD2") (pin "C") (pinfunction "C_C") (pintype "passive"))
      (node (ref "SJ2") (pin "2") (pinfunction "2_2") (pintype "passive"))
      (node (ref "TXD2") (pin "C") (pinfunction "C_C") (pintype "passive"))
    )
    (net (code "79") (name "/SER3_TRC") (class "Default")
      (node (ref "RXD3") (pin "C") (pinfunction "C_C") (pintype "passive"))
      (node (ref "SJ3") (pin "2") (pinfunction "2_2") (pintype "passive"))
      (node (ref "TXD3") (pin "C") (pinfunction "C_C") (pintype "passive"))
    )
    (net (code "80") (name "/STA_LED_RES") (class "Default")
      (node (ref "LED10") (pin "A") (pinfunction "A_A") (pintype "passive"))
      (node (ref "R1") (pin "1") (pinfunction "1_1") (pintype "passive"))
    )
    (net (code "81") (name "/STA_LED_TRC") (class "Default")
      (node (ref "R1") (pin "2") (pinfunction "2_2") (pintype "passive"))
      (node (ref "SJ4") (pin "2") (pinfunction "2_2") (pintype "passive"))
    )
    (net (code "82") (name "/SW") (class "Default")
      (node (ref "C3") (pin "2") (pinfunction "2_2") (pintype "passive"))
      (node (ref "D3") (pin "P$1") (pinfunction "K_P$1") (pintype "bidirectional"))
      (node (ref "IC1") (pin "6") (pinfunction "SW_6") (pintype "output"))
      (node (ref "L2") (pin "P$1") (pinfunction "1_P$1") (pintype "passive"))
    )
    (net (code "83") (name "/TEENSY_RX1") (class "Default")
      (node (ref "JP5") (pin "1") (pinfunction "1_1") (pintype "passive"))
      (node (ref "JP8") (pin "6") (pinfunction "6_6") (pintype "passive"))
      (node (ref "MDL1") (pin "16") (pinfunction "TXD_16") (pintype "bidirectional"))
      (node (ref "RN3") (pin "1") (pinfunction "1_1") (pintype "passive"))
      (node (ref "TEENSY_3.1/3.2") (pin "0") (pinfunction "0/RX1/T_0") (pintype "bidirectional"))
    )
    (net (code "84") (name "/TEENSY_TX1") (class "Default")
      (node (ref "JP5") (pin "2") (pinfunction "2_2") (pintype "passive"))
      (node (ref "JP8") (pin "8") (pinfunction "8_8") (pintype "passive"))
      (node (ref "MDL1") (pin "15") (pinfunction "RXD_15") (pintype "bidirectional"))
      (node (ref "RN3") (pin "2") (pinfunction "1_2") (pintype "passive"))
      (node (ref "TEENSY_3.1/3.2") (pin "1") (pinfunction "1/TX1/T_1") (pintype "bidirectional"))
    )
    (net (code "85") (name "/TX1L") (class "Default")
      (node (ref "Q1") (pin "6") (pinfunction "D_6") (pintype "passive"))
      (node (ref "RN7") (pin "8") (pinfunction "2_8") (pintype "passive"))
    )
    (net (code "86") (name "/TX1_LED_RES") (class "Default")
      (node (ref "RN7") (pin "1") (pinfunction "1_1") (pintype "passive"))
      (node (ref "TXD1") (pin "A") (pinfunction "A_A") (pintype "passive"))
    )
    (net (code "87") (name "/TX1_Q1A_GATE") (class "Default")
      (node (ref "Q1") (pin "2") (pinfunction "G_2") (pintype "passive"))
      (node (ref "RN3") (pin "7") (pinfunction "2_7") (pintype "passive"))
      (node (ref "RN6") (pin "6") (pinfunction "2_6") (pintype "passive"))
    )
    (net (code "88") (name "/TX2L") (class "Default")
      (node (ref "Q2") (pin "6") (pinfunction "D_6") (pintype "passive"))
      (node (ref "RN7") (pin "6") (pinfunction "2_6") (pintype "passive"))
    )
    (net (code "89") (name "/TX2_LED_RES") (class "Default")
      (node (ref "RN7") (pin "3") (pinfunction "1_3") (pintype "passive"))
      (node (ref "TXD2") (pin "A") (pinfunction "A_A") (pintype "passive"))
    )
    (net (code "90") (name "/TX2_Q2A_GATE") (class "Default")
      (node (ref "Q2") (pin "2") (pinfunction "G_2") (pintype "passive"))
      (node (ref "RN3") (pin "5") (pinfunction "2_5") (pintype "passive"))
      (node (ref "RN6") (pin "8") (pinfunction "2_8") (pintype "passive"))
    )
    (net (code "91") (name "/TX3L") (class "Default")
      (node (ref "Q3") (pin "6") (pinfunction "D_6") (pintype "passive"))
      (node (ref "RN1") (pin "7") (pinfunction "2_7") (pintype "passive"))
    )
    (net (code "92") (name "/TX3_LED_RES") (class "Default")
      (node (ref "RN1") (pin "2") (pinfunction "1_2") (pintype "passive"))
      (node (ref "TXD3") (pin "A") (pinfunction "A_A") (pintype "passive"))
    )
    (net (code "93") (name "/TX3_Q3A_GATE") (class "Default")
      (node (ref "Q3") (pin "2") (pinfunction "G_2") (pintype "passive"))
      (node (ref "RN8") (pin "2") (pinfunction "1_2") (pintype "passive"))
      (node (ref "RN9") (pin "3") (pinfunction "2_3") (pintype "passive"))
    )
    (net (code "94") (name "/TX3_RX3_PU_SJ") (class "Default")
      (node (ref "RN9") (pin "1") (pinfunction "1_1") (pintype "passive"))
      (node (ref "RN9") (pin "2") (pinfunction "1_2") (pintype "passive"))
      (node (ref "SJ6") (pin "2") (pinfunction "2_2") (pintype "passive"))
    )
    (net (code "95") (name "/VBAT") (class "Default")
      (node (ref "CR2032") (pin "POSITIVE@1") (pinfunction "+_POSITIVE@1") (pintype "power_in"))
      (node (ref "CR2032") (pin "POSITIVE@2") (pinfunction "+_POSITIVE@2") (pintype "power_in"))
      (node (ref "CR2032") (pin "POSITIVE@3") (pinfunction "+_POSITIVE@3") (pintype "power_in"))
      (node (ref "CR2032") (pin "POSITIVE@4") (pinfunction "+_POSITIVE@4") (pintype "power_in"))
      (node (ref "TEENSY_3.1/3.2") (pin "VBAT") (pinfunction "VBAT_VBAT") (pintype "power_in"))
    )
    (net (code "96") (name "/VIN") (class "Default")
      (node (ref "C1") (pin "+") (pinfunction "+_+") (pintype "passive"))
      (node (ref "C2") (pin "+") (pinfunction "+_+") (pintype "passive"))
      (node (ref "D1") (pin "P$1") (pinfunction "K_P$1") (pintype "bidirectional"))
      (node (ref "IC1") (pin "5") (pinfunction "VIN_5") (pintype "input"))
      (node (ref "JP11") (pin "8") (pinfunction "8_8") (pintype "passive"))
      (node (ref "R2") (pin "2") (pinfunction "2_2") (pintype "passive"))
    )
    (net (code "97") (name "/VIN+") (class "Default")
      (node (ref "L1") (pin "2") (pinfunction "2_2") (pintype "passive"))
      (node (ref "VIN") (pin "2") (pinfunction "2_2") (pintype "passive"))
      (node (ref "X1") (pin "2") (pinfunction "2_2") (pintype "power_in"))
    )
    (net (code "98") (name "/VIN2_GND") (class "Default")
      (node (ref "VIN") (pin "1") (pinfunction "1_1") (pintype "passive"))
      (node (ref "X1") (pin "1") (pinfunction "1_1") (pintype "power_in"))
    )
    (net (code "99") (name "/VUSB") (class "Default")
      (node (ref "PAD2") (pin "1") (pinfunction "P_1") (pintype "passive"))
      (node (ref "Q4") (pin "3") (pinfunction "D_3") (pintype "passive"))
      (node (ref "TEENSY_3.1/3.2") (pin "VUSB") (pinfunction "VUSB_VUSB") (pintype "power_in"))
    )
    (net (code "100") (name "GND") (class "Default")
      (node (ref "C1") (pin "-") (pinfunction "-_-") (pintype "passive"))
      (node (ref "C10") (pin "2") (pinfunction "2_2") (pintype "passive"))
      (node (ref "C2") (pin "-") (pinfunction "-_-") (pintype "passive"))
      (node (ref "C5") (pin "-") (pinfunction "-_-") (pintype "passive"))
      (node (ref "C6") (pin "2") (pinfunction "2_2") (pintype "passive"))
      (node (ref "C7") (pin "1") (pinfunction "1_1") (pintype "passive"))
      (node (ref "C8") (pin "-") (pinfunction "-_-") (pintype "passive"))
      (node (ref "C9") (pin "2") (pinfunction "2_2") (pintype "passive"))
      (node (ref "CR2032") (pin "NEGATIVE") (pinfunction "-_NEGATIVE") (pintype "power_in"))
      (node (ref "D13") (pin "C") (pinfunction "C_C") (pintype "passive"))
      (node (ref "D3") (pin "P$2") (pinfunction "A_P$2") (pintype "bidirectional"))
      (node (ref "ESP-PGM") (pin "4") (pinfunction "4_4") (pintype "passive"))
      (node (ref "ESP-RST") (pin "2") (pinfunction "2_2") (pintype "passive"))
      (node (ref "HC-05/06") (pin "4") (pinfunction "4_4") (pintype "passive"))
      (node (ref "IC1") (pin "2") (pinfunction "GND_2") (pintype "power_in"))
      (node (ref "IC2") (pin "1") (pinfunction "GND_1") (pintype "power_in"))
      (node (ref "JP11") (pin "6") (pinfunction "6_6") (pintype "passive"))
      (node (ref "JP11") (pin "7") (pinfunction "7_7") (pintype "passive"))
      (node (ref "JP4") (pin "7") (pinfunction "7_7") (pintype "passive"))
      (node (ref "JP8") (pin "24") (pinfunction "24_24") (pintype "passive"))
      (node (ref "JP8") (pin "25") (pinfunction "25_25") (pintype "passive"))
      (node (ref "JP8") (pin "35") (pinfunction "35_35") (pintype "passive"))
      (node (ref "JP8") (pin "36") (pinfunction "36_36") (pintype "passive"))
      (node (ref "LED10") (pin "C") (pinfunction "C_C") (pintype "passive"))
      (node (ref "MDL1") (pin "9") (pinfunction "GND_9") (pintype "bidirectional"))
      (node (ref "PWR") (pin "C") (pinfunction "C_C") (pintype "passive"))
      (node (ref "Q4") (pin "1") (pinfunction "G_1") (pintype "passive"))
      (node (ref "R4") (pin "2") (pinfunction "2_2") (pintype "passive"))
      (node (ref "RESET") (pin "2") (pinfunction "2_2") (pintype "passive"))
      (node (ref "RN4") (pin "3") (pinfunction "2_3") (pintype "passive"))
      (node (ref "SJ1") (pin "1") (pinfunction "1_1") (pintype "passive"))
      (node (ref "SJ2") (pin "1") (pinfunction "1_1") (pintype "passive"))
      (node (ref "SJ3") (pin "1") (pinfunction "1_1") (pintype "passive"))
      (node (ref "SPI") (pin "6") (pinfunction "6_6") (pintype "passive"))
      (node (ref "TEENSY_3.1/3.2") (pin "AGND") (pinfunction "AGND_AGND") (pintype "power_in"))
      (node (ref "TEENSY_3.1/3.2") (pin "GND") (pinfunction "GND_GND") (pintype "power_in"))
      (node (ref "TEENSY_3.1/3.2") (pin "GND1") (pinfunction "GND_GND1") (pintype "power_in"))
      (node (ref "TEENSY_3.1/3.2") (pin "GND2") (pinfunction "GND_GND2") (pintype "power_in"))
      (node (ref "X1") (pin "3") (pinfunction "3_3") (pintype "power_in"))
    )
    (net (code "101") (name "Net-(D1-A)") (class "Default")
      (node (ref "D1") (pin "P$2") (pinfunction "A_P$2") (pintype "bidirectional"))
      (node (ref "L1") (pin "1") (pinfunction "1_1") (pintype "passive"))
    )
    (net (code "102") (name "Net-(D13-PadA)") (class "Default")
      (node (ref "D13") (pin "A") (pinfunction "A_A") (pintype "passive"))
      (node (ref "RN1") (pin "1") (pinfunction "1_1") (pintype "passive"))
    )
    (net (code "103") (name "Net-(RN1D-2)") (class "Default")
      (node (ref "PWR") (pin "A") (pinfunction "A_A") (pintype "passive"))
      (node (ref "RN1") (pin "5") (pinfunction "2_5") (pintype "passive"))
    )
    (net (code "104") (name "Net-(RN6B-1)") (class "Default")
      (node (ref "RN6") (pin "1") (pinfunction "1_1") (pintype "passive"))
      (node (ref "RN6") (pin "2") (pinfunction "1_2") (pintype "passive"))
      (node (ref "RN6") (pin "3") (pinfunction "1_3") (pintype "passive"))
      (node (ref "RN6") (pin "4") (pinfunction "1_4") (pintype "passive"))
      (node (ref "SJ5") (pin "1") (pinfunction "1_1") (pintype "passive"))
    )
    (net (code "105") (name "unconnected-(ESP-PGM-Pad1)") (class "Default")
      (node (ref "ESP-PGM") (pin "1") (pinfunction "1_1") (pintype "passive"))
    )
    (net (code "106") (name "unconnected-(ESP-PGM-Pad3)") (class "Default")
      (node (ref "ESP-PGM") (pin "3") (pinfunction "3_3") (pintype "passive"))
    )
    (net (code "107") (name "unconnected-(ESP-RST-Pad1)") (class "Default")
      (node (ref "ESP-RST") (pin "1") (pinfunction "1_1") (pintype "passive"))
    )
    (net (code "108") (name "unconnected-(ESP-RST-Pad3)") (class "Default")
      (node (ref "ESP-RST") (pin "3") (pinfunction "3_3") (pintype "passive"))
    )
    (net (code "109") (name "unconnected-(HC-PGM-Pad1)") (class "Default")
      (node (ref "HC-PGM") (pin "1") (pinfunction "1_1") (pintype "passive"))
    )
    (net (code "110") (name "unconnected-(HC-PGM-Pad3)") (class "Default")
      (node (ref "HC-PGM") (pin "3") (pinfunction "3_3") (pintype "passive"))
    )
    (net (code "111") (name "unconnected-(JP8-Pad33)") (class "Default")
      (node (ref "JP8") (pin "33") (pinfunction "33_33") (pintype "passive"))
    )
    (net (code "112") (name "unconnected-(JP8-Pad34)") (class "Default")
      (node (ref "JP8") (pin "34") (pinfunction "34_34") (pintype "passive"))
    )
    (net (code "113") (name "unconnected-(JP11-Pad1)") (class "Default")
      (node (ref "JP11") (pin "1") (pinfunction "1_1") (pintype "passive"))
    )
    (net (code "114") (name "unconnected-(RESET-Pad1)") (class "Default")
      (node (ref "RESET") (pin "1") (pinfunction "1_1") (pintype "passive"))
    )
    (net (code "115") (name "unconnected-(RESET-Pad4)") (class "Default")
      (node (ref "RESET") (pin "4") (pinfunction "4_4") (pintype "passive"))
    )
  )
)
